# RTC_Module.net
KiCad netlist of a schematic drawn in Altium Designer
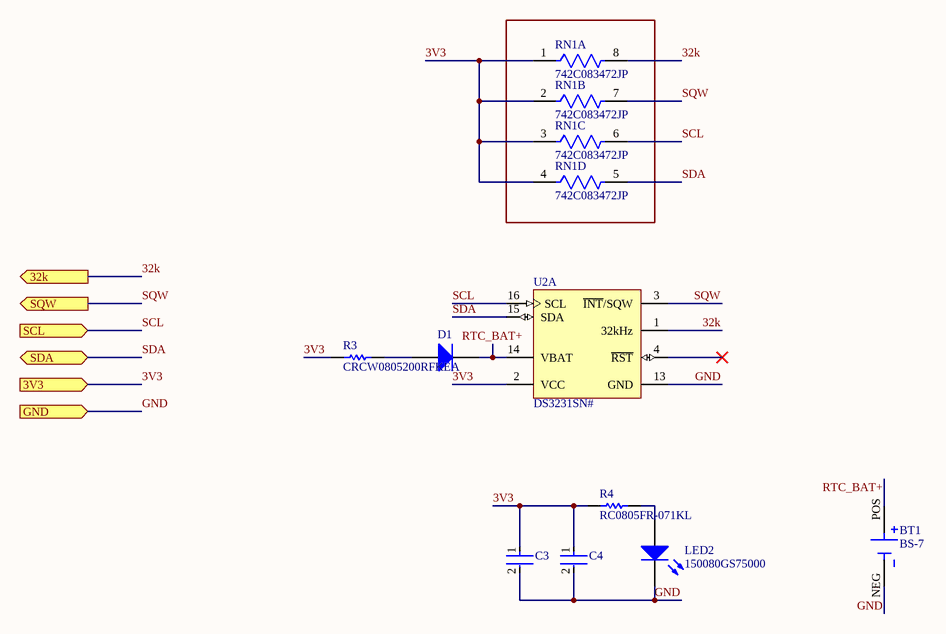
[diagram p0: RTC_Module.SchDoc]

(export (version "E")
  (design (tool "Eeschema 10.0.6"))
  (components
    (comp (ref "BT1")
      (value "BS-7")
      (footprint "BAT_BS-7")
      (description "BATTERY HOLDER COIN 20MM PC PIN")
      (fields (field (name "MF") "MPD _Memory"))
      (libsource (lib "BS-7") (part "BS-7"))
    )
    (comp (ref "C3")
      (value "C0805C104K5RACTU")
      (footprint "FP-C0805C-DN-MFG")
      (description "CAP CER 0.1UF 50V X7R 0805")
      (fields
        (field (name "MANUFACTURER") "KEMET")
        (field (name "OCTOPART") "https://octopart.com/c0805c104k5ractu-kemet-143926")
      )
      (libsource (lib "Altium Content Vault") (part "b4654b650e69147ec39a6b967a45e02"))
    )
    (comp (ref "C4")
      (value "C0805C104K5RACTU")
      (footprint "FP-C0805C-DN-MFG")
      (description "CAP CER 0.1UF 50V X7R 0805")
      (fields
        (field (name "MANUFACTURER") "KEMET")
        (field (name "OCTOPART") "https://octopart.com/c0805c104k5ractu-kemet-143926")
      )
      (libsource (lib "Altium Content Vault") (part "b4654b650e69147ec39a6b967a45e02"))
    )
    (comp (ref "D1")
      (value "1N4148W-7-F")
      (footprint "DIOD-SOD123-2_V")
      (description "Fast Switching Diode, 100 V, 0.15 A, -65 to 150 degC, 2-Pin?SOD123, RoHS, Tape and Reel")
      (fields (field (name "MANUFACTURER") "DiodesIncorporated"))
      (libsource (lib "Altium Content Vault") (part "D-AK-2"))
    )
    (comp (ref "LED2")
      (value "150080GS75000")
      (footprint "0805_A")
      (description "SMD mono-color Chip LED, WL-SMCW, Green")
      (fields (field (name "MANUFACTURER") "Wuerth Elektronik"))
      (libsource (lib "Altium Content Vault") (part "WE-LED_K1A2-2"))
    )
    (comp (ref "R3")
      (value "CRCW0805200RFKEA")
      (footprint "RESC2013X50X30NL20T20")
      (fields (field (name "MANUFACTURER") "Vishay Dale"))
      (libsource (lib "Altium Content Vault") (part "RES"))
    )
    (comp (ref "R4")
      (value "RC0805FR-071KL")
      (footprint "RESC2013X60X35ML10T20")
      (description "Chip Resistor, 1 KOhm, +/- 1%, 125 mW, -55 to 155 degC, 0805 (2012 Metric), RoHS, Tape and Reel")
      (fields (field (name "TOLERANCE") "1%") (field (name "MANUFACTURER") "Yageo"))
      (libsource (lib "Altium Content Vault") (part "RES-2"))
    )
    (comp (ref "RN1")
      (value "742C083472JP")
      (footprint "FP-742C083-MFG")
      (description "RES ARRAY 4 RES 4.7K OHM 1206")
      (fields (field (name "TOLERANCE") "5%"))
      (libsource (lib "Altium Content Vault") (part "46c0e806a6f3a765a2d55930d12d044"))
    )
    (comp (ref "U2")
      (value "DS3231SN#")
      (footprint "W16#H2_M")
      (libsource (lib "Altium Content Vault") (part "MAX-RTC-16-DS3231S-W16#H2"))
    )
  )
  (nets
    (net (code "1") (name "/3V3") (class "Default")
      (node (ref "C3") (pin "1") (pinfunction "1_1") (pintype "passive"))
      (node (ref "C4") (pin "1") (pinfunction "1_1") (pintype "passive"))
      (node (ref "R3") (pin "2") (pinfunction "2_2") (pintype "passive"))
      (node (ref "R4") (pin "2") (pinfunction "2_2") (pintype "passive"))
      (node (ref "RN1") (pin "1") (pinfunction "1_1") (pintype "passive"))
      (node (ref "RN1") (pin "2") (pinfunction "2_2") (pintype "passive"))
      (node (ref "RN1") (pin "3") (pinfunction "3_3") (pintype "passive"))
      (node (ref "RN1") (pin "4") (pinfunction "4_4") (pintype "passive"))
      (node (ref "U2") (pin "2") (pinfunction "VCC_2") (pintype "power_in"))
    )
    (net (code "2") (name "/32k") (class "Default")
      (node (ref "RN1") (pin "8") (pinfunction "8_8") (pintype "passive"))
      (node (ref "U2") (pin "1") (pinfunction "32kHz_1") (pintype "open_collector"))
    )
    (net (code "3") (name "/GND") (class "Default")
      (node (ref "BT1") (pin "NEG") (pinfunction "NEG_NEG") (pintype "passive"))
      (node (ref "C3") (pin "2") (pinfunction "2_2") (pintype "passive"))
      (node (ref "C4") (pin "2") (pinfunction "2_2") (pintype "passive"))
      (node (ref "LED2") (pin "1") (pinfunction "K_1") (pintype "passive"))
      (node (ref "U2") (pin "13") (pinfunction "GND_13") (pintype "power_in"))
    )
    (net (code "4") (name "/RTC_BAT+") (class "Default")
      (node (ref "BT1") (pin "POS") (pinfunction "POS_POS") (pintype "passive"))
      (node (ref "D1") (pin "2") (pinfunction "K_2") (pintype "passive"))
      (node (ref "U2") (pin "14") (pinfunction "VBAT_14") (pintype "power_in"))
    )
    (net (code "5") (name "/SCL") (class "Default")
      (node (ref "RN1") (pin "6") (pinfunction "6_6") (pintype "passive"))
      (node (ref "U2") (pin "16") (pinfunction "SCL_16") (pintype "input"))
    )
    (net (code "6") (name "/SDA") (class "Default")
      (node (ref "RN1") (pin "5") (pinfunction "5_5") (pintype "passive"))
      (node (ref "U2") (pin "15") (pinfunction "SDA_15") (pintype "bidirectional"))
    )
    (net (code "7") (name "/SQW") (class "Default")
      (node (ref "RN1") (pin "7") (pinfunction "7_7") (pintype "passive"))
      (node (ref "U2") (pin "3") (pinfunction "~{INT}/SQW_3") (pintype "open_collector"))
    )
    (net (code "8") (name "Net-(D1-A)") (class "Default")
      (node (ref "D1") (pin "1") (pinfunction "A_1") (pintype "passive"))
      (node (ref "R3") (pin "1") (pinfunction "1_1") (pintype "passive"))
    )
    (net (code "9") (name "Net-(LED2-A)") (class "Default")
      (node (ref "LED2") (pin "2") (pinfunction "A_2") (pintype "passive"))
      (node (ref "R4") (pin "1") (pinfunction "1_1") (pintype "passive"))
    )
    (net (code "10") (name "unconnected-(U2A-~{RST}-Pad4)") (class "Default")
      (node (ref "U2") (pin "4") (pinfunction "~{RST}_4") (pintype "bidirectional+no_connect"))
    )
  )
)
